# FiltroRF.net
KiCad netlist of a schematic drawn in Altium Designer
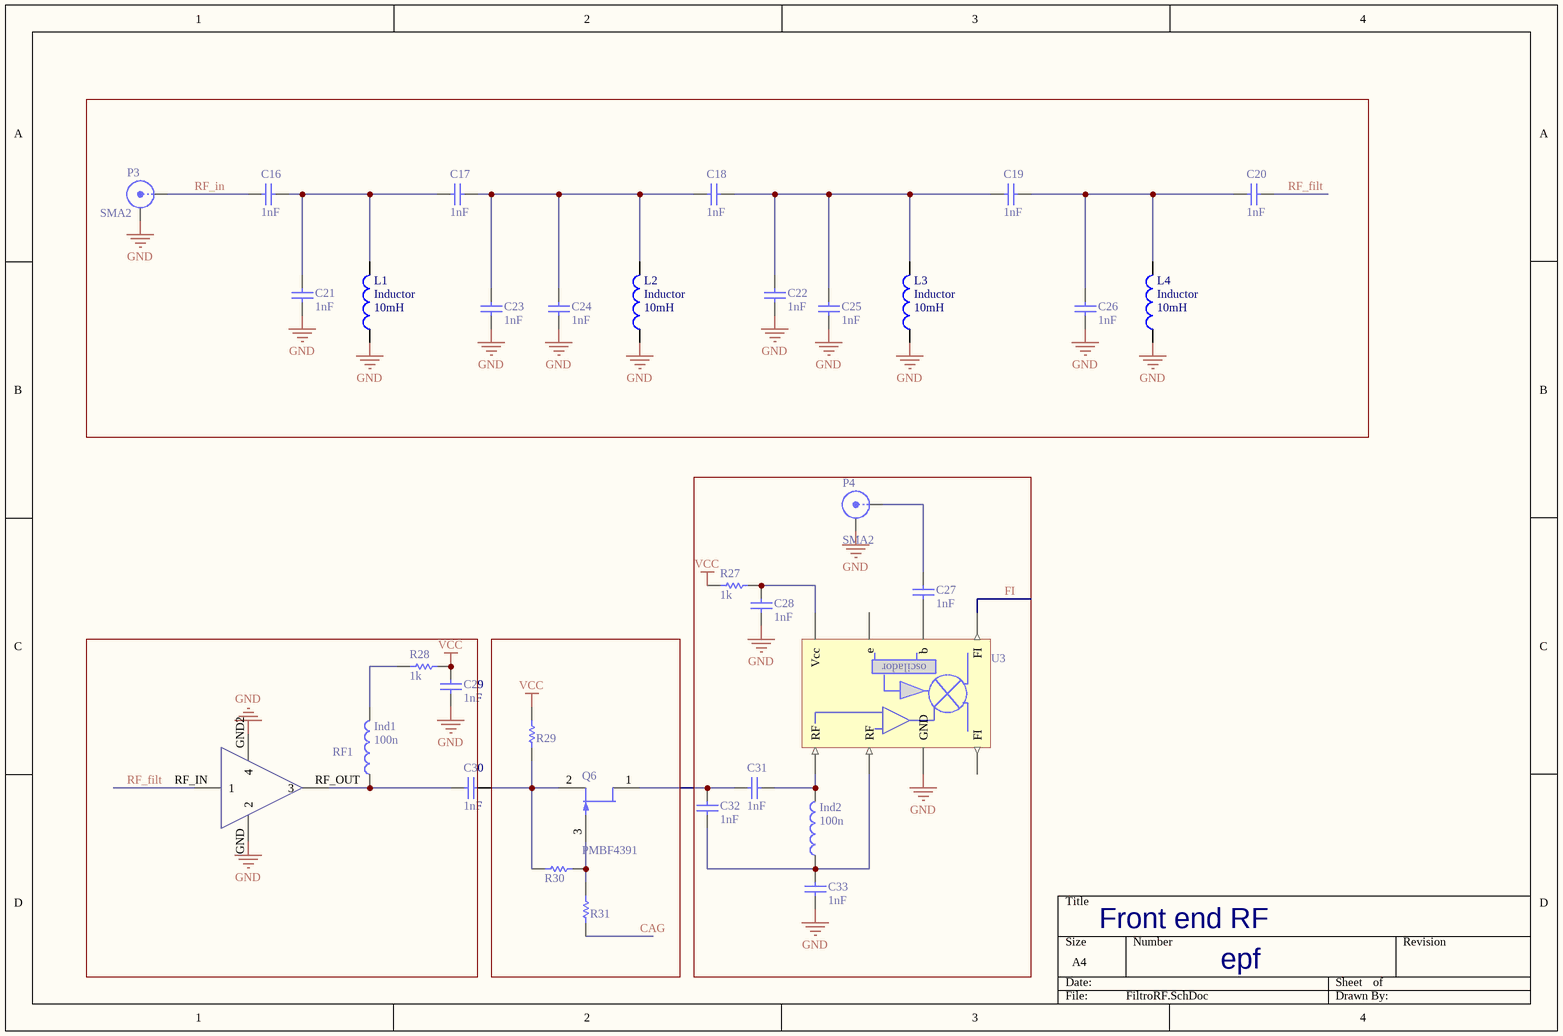
[diagram p0: FiltroRF.SchDoc]

(export (version "E")
  (design (tool "Eeschema 10.0.6"))
  (components
    (comp (ref "C16")
      (value "1nF")
      (footprint "0805_CAP")
      (fields (field (name "Comment") "Capacitor"))
      (libsource (lib "epf") (part "Cap"))
    )
    (comp (ref "C17")
      (value "1nF")
      (footprint "0805_CAP")
      (fields (field (name "Comment") "Capacitor"))
      (libsource (lib "epf") (part "Cap"))
    )
    (comp (ref "C18")
      (value "1nF")
      (footprint "0805_CAP")
      (fields (field (name "Comment") "Capacitor"))
      (libsource (lib "epf") (part "Cap"))
    )
    (comp (ref "C19")
      (value "1nF")
      (footprint "0805_CAP")
      (fields (field (name "Comment") "Capacitor"))
      (libsource (lib "epf") (part "Cap"))
    )
    (comp (ref "C20")
      (value "1nF")
      (footprint "0805_CAP")
      (fields (field (name "Comment") "Capacitor"))
      (libsource (lib "epf") (part "Cap"))
    )
    (comp (ref "C21")
      (value "1nF")
      (footprint "0805_CAP")
      (fields (field (name "Comment") "Capacitor"))
      (libsource (lib "epf") (part "Cap"))
    )
    (comp (ref "C22")
      (value "1nF")
      (footprint "0805_CAP")
      (fields (field (name "Comment") "Capacitor"))
      (libsource (lib "epf") (part "Cap"))
    )
    (comp (ref "C23")
      (value "1nF")
      (footprint "0805_CAP")
      (fields (field (name "Comment") "Capacitor"))
      (libsource (lib "epf") (part "Cap"))
    )
    (comp (ref "C24")
      (value "1nF")
      (footprint "0805_CAP")
      (fields (field (name "Comment") "Capacitor"))
      (libsource (lib "epf") (part "Cap"))
    )
    (comp (ref "C25")
      (value "1nF")
      (footprint "0805_CAP")
      (fields (field (name "Comment") "Capacitor"))
      (libsource (lib "epf") (part "Cap"))
    )
    (comp (ref "C26")
      (value "1nF")
      (footprint "0805_CAP")
      (fields (field (name "Comment") "Capacitor"))
      (libsource (lib "epf") (part "Cap"))
    )
    (comp (ref "C27")
      (value "1nF")
      (footprint "0805_CAP")
      (fields (field (name "Comment") "Capacitor"))
      (libsource (lib "epf") (part "Cap"))
    )
    (comp (ref "C28")
      (value "1nF")
      (footprint "0805_CAP")
      (fields (field (name "Comment") "Capacitor"))
      (libsource (lib "epf") (part "Cap"))
    )
    (comp (ref "C29")
      (value "1nF")
      (footprint "0805_CAP")
      (fields (field (name "Comment") "Capacitor"))
      (libsource (lib "epf") (part "Cap"))
    )
    (comp (ref "C30")
      (value "1nF")
      (footprint "0805_CAP")
      (fields (field (name "Comment") "Capacitor"))
      (libsource (lib "epf") (part "Cap"))
    )
    (comp (ref "C31")
      (value "1nF")
      (footprint "0805_CAP")
      (fields (field (name "Comment") "Capacitor"))
      (libsource (lib "epf") (part "Cap"))
    )
    (comp (ref "C32")
      (value "1nF")
      (footprint "0805_CAP")
      (fields (field (name "Comment") "Capacitor"))
      (libsource (lib "epf") (part "Cap"))
    )
    (comp (ref "C33")
      (value "1nF")
      (footprint "0805_CAP")
      (fields (field (name "Comment") "Capacitor"))
      (libsource (lib "epf") (part "Cap"))
    )
    (comp (ref "Ind1")
      (value "Ind2")
      (footprint "NTH12_2")
      (fields (field (name "VALOR") "100n"))
      (libsource (lib "epf") (part "Ind2"))
    )
    (comp (ref "Ind2")
      (value "Ind2")
      (footprint "Ind_3mm")
      (fields (field (name "VALOR") "100n"))
      (libsource (lib "epf") (part "Ind2"))
    )
    (comp (ref "L1")
      (value "Inductor")
      (footprint "INDC3216AL")
      (fields (field (name "ALTIUM_VALUE") "10mH") (field (name "PUBLISHER") "Altium Limited"))
      (libsource (lib "Miscellaneous Devices") (part "Inductor"))
    )
    (comp (ref "L2")
      (value "Inductor")
      (footprint "INDC3216AL")
      (fields (field (name "ALTIUM_VALUE") "10mH") (field (name "PUBLISHER") "Altium Limited"))
      (libsource (lib "Miscellaneous Devices") (part "Inductor"))
    )
    (comp (ref "L3")
      (value "Inductor")
      (footprint "INDC3216AL")
      (fields (field (name "ALTIUM_VALUE") "10mH") (field (name "PUBLISHER") "Altium Limited"))
      (libsource (lib "Miscellaneous Devices") (part "Inductor"))
    )
    (comp (ref "L4")
      (value "Inductor")
      (footprint "INDC3216AL")
      (fields (field (name "ALTIUM_VALUE") "10mH") (field (name "PUBLISHER") "Altium Limited"))
      (libsource (lib "Miscellaneous Devices") (part "Inductor"))
    )
    (comp (ref "P3")
      (value "SMA2")
      (footprint "SMAL_Antena")
      (description "BNC Elbow Connector")
      (fields (field (name "PUBLISHER") "Altium Limited"))
      (libsource (lib "epf") (part "SMA2"))
    )
    (comp (ref "P4")
      (value "SMA2")
      (footprint "SMAL2")
      (description "BNC Elbow Connector")
      (fields (field (name "PUBLISHER") "Altium Limited"))
      (libsource (lib "epf") (part "SMA2"))
    )
    (comp (ref "Q6")
      (value "PMBF4391")
      (footprint "SOT23")
      (description "N-channel Silicon Junction Field-effect Transistor")
      (fields (field (name "PUBLISHER") "Altium Limited"))
      (libsource (lib "Philips Discrete JFET") (part "PMBF4391"))
    )
    (comp (ref "R27")
      (value "1k")
      (footprint "0805_RES")
      (fields (field (name "Comment") "Resistor"))
      (libsource (lib "epf") (part "Res"))
    )
    (comp (ref "R28")
      (value "1k")
      (footprint "0805_RES")
      (fields (field (name "Comment") "Resistor"))
      (libsource (lib "epf") (part "Res"))
    )
    (comp (ref "R29") (value "Resistor") (footprint "0805_RES") (libsource (lib "epf") (part "Res")))
    (comp (ref "R30") (value "Resistor") (footprint "0805_RES") (libsource (lib "epf") (part "Res")))
    (comp (ref "R31") (value "Resistor") (footprint "0805_RES") (libsource (lib "epf") (part "Res")))
    (comp (ref "RF1") (value "MAR-1SM") (footprint "WW107") (libsource (lib "epf") (part "MAR-1SM")))
    (comp (ref "U3")
      (value "SA602")
      (footprint "SO-8_2")
      (description "Mezclador 500MHz")
      (libsource (lib "epf") (part "SA602A"))
    )
  )
  (nets
    (net (code "1") (name "/CAG") (class "Default")
      (node (ref "R31") (pin "1") (pinfunction "1_1") (pintype "passive"))
    )
    (net (code "2") (name "/FI") (class "Default")
      (node (ref "U3") (pin "5") (pinfunction "FI_5") (pintype "output"))
    )
    (net (code "3") (name "/RF_filt") (class "Default")
      (node (ref "C20") (pin "1") (pinfunction "1_1") (pintype "passive"))
      (node (ref "RF1") (pin "RF_IN") (pinfunction "1_RF_IN") (pintype "passive"))
    )
    (net (code "4") (name "/RF_in") (class "Default")
      (node (ref "C16") (pin "2") (pinfunction "2_2") (pintype "passive"))
      (node (ref "P3") (pin "1") (pinfunction "X_1") (pintype "passive"))
    )
    (net (code "5") (name "GND") (class "Default")
      (node (ref "C21") (pin "2") (pinfunction "2_2") (pintype "passive"))
      (node (ref "C22") (pin "1") (pinfunction "1_1") (pintype "passive"))
      (node (ref "C23") (pin "1") (pinfunction "1_1") (pintype "passive"))
      (node (ref "C24") (pin "1") (pinfunction "1_1") (pintype "passive"))
      (node (ref "C25") (pin "1") (pinfunction "1_1") (pintype "passive"))
      (node (ref "C26") (pin "2") (pinfunction "2_2") (pintype "passive"))
      (node (ref "C28") (pin "1") (pinfunction "1_1") (pintype "passive"))
      (node (ref "C29") (pin "1") (pinfunction "1_1") (pintype "passive"))
      (node (ref "C33") (pin "2") (pinfunction "2_2") (pintype "passive"))
      (node (ref "L1") (pin "1") (pinfunction "1_1") (pintype "passive"))
      (node (ref "L2") (pin "1") (pinfunction "1_1") (pintype "passive"))
      (node (ref "L3") (pin "1") (pinfunction "1_1") (pintype "passive"))
      (node (ref "L4") (pin "1") (pinfunction "1_1") (pintype "passive"))
      (node (ref "P3") (pin "0") (pinfunction "Y_0") (pintype "passive"))
      (node (ref "P4") (pin "0") (pinfunction "Y_0") (pintype "passive"))
      (node (ref "RF1") (pin "GND") (pinfunction "2_GND") (pintype "passive"))
      (node (ref "RF1") (pin "GND2") (pinfunction "4_GND2") (pintype "passive"))
      (node (ref "U3") (pin "3") (pinfunction "GND_3") (pintype "passive"))
    )
    (net (code "6") (name "Net-(C16-Pad1)") (class "Default")
      (node (ref "C16") (pin "1") (pinfunction "1_1") (pintype "passive"))
      (node (ref "C17") (pin "2") (pinfunction "2_2") (pintype "passive"))
      (node (ref "C21") (pin "1") (pinfunction "1_1") (pintype "passive"))
      (node (ref "L1") (pin "2") (pinfunction "2_2") (pintype "passive"))
    )
    (net (code "7") (name "Net-(C17-Pad1)") (class "Default")
      (node (ref "C17") (pin "1") (pinfunction "1_1") (pintype "passive"))
      (node (ref "C18") (pin "1") (pinfunction "1_1") (pintype "passive"))
      (node (ref "C23") (pin "2") (pinfunction "2_2") (pintype "passive"))
      (node (ref "C24") (pin "2") (pinfunction "2_2") (pintype "passive"))
      (node (ref "L2") (pin "2") (pinfunction "2_2") (pintype "passive"))
    )
    (net (code "8") (name "Net-(C18-Pad2)") (class "Default")
      (node (ref "C18") (pin "2") (pinfunction "2_2") (pintype "passive"))
      (node (ref "C19") (pin "1") (pinfunction "1_1") (pintype "passive"))
      (node (ref "C22") (pin "2") (pinfunction "2_2") (pintype "passive"))
      (node (ref "C25") (pin "2") (pinfunction "2_2") (pintype "passive"))
      (node (ref "L3") (pin "2") (pinfunction "2_2") (pintype "passive"))
    )
    (net (code "9") (name "Net-(C19-Pad2)") (class "Default")
      (node (ref "C19") (pin "2") (pinfunction "2_2") (pintype "passive"))
      (node (ref "C20") (pin "2") (pinfunction "2_2") (pintype "passive"))
      (node (ref "C26") (pin "1") (pinfunction "1_1") (pintype "passive"))
      (node (ref "L4") (pin "2") (pinfunction "2_2") (pintype "passive"))
    )
    (net (code "10") (name "Net-(C31-Pad1)") (class "Default")
      (node (ref "C31") (pin "1") (pinfunction "1_1") (pintype "passive"))
      (node (ref "Ind2") (pin "2") (pinfunction "2_2") (pintype "passive"))
      (node (ref "U3") (pin "1") (pinfunction "RF_1") (pintype "input"))
    )
    (net (code "11") (name "Net-(C32-Pad2)") (class "Default")
      (node (ref "C32") (pin "2") (pinfunction "2_2") (pintype "passive"))
      (node (ref "C33") (pin "1") (pinfunction "1_1") (pintype "passive"))
      (node (ref "Ind2") (pin "1") (pinfunction "1_1") (pintype "passive"))
      (node (ref "U3") (pin "2") (pinfunction "RF_2") (pintype "input"))
    )
    (net (code "12") (name "Net-(Ind1-Pad2)") (class "Default")
      (node (ref "Ind1") (pin "2") (pinfunction "2_2") (pintype "passive"))
      (node (ref "R28") (pin "1") (pinfunction "1_1") (pintype "passive"))
    )
    (net (code "13") (name "Net-(P4-X)") (class "Default")
      (node (ref "C27") (pin "2") (pinfunction "2_2") (pintype "passive"))
      (node (ref "P4") (pin "1") (pinfunction "X_1") (pintype "passive"))
    )
    (net (code "14") (name "Net-(Q6-D)") (class "Default")
      (node (ref "C31") (pin "2") (pinfunction "2_2") (pintype "passive"))
      (node (ref "C32") (pin "1") (pinfunction "1_1") (pintype "passive"))
      (node (ref "Q6") (pin "1") (pinfunction "D_1") (pintype "passive"))
    )
    (net (code "15") (name "Net-(Q6-G)") (class "Default")
      (node (ref "Q6") (pin "3") (pinfunction "G_3") (pintype "passive"))
      (node (ref "R30") (pin "1") (pinfunction "1_1") (pintype "passive"))
      (node (ref "R31") (pin "2") (pinfunction "2_2") (pintype "passive"))
    )
    (net (code "16") (name "Net-(Q6-S)") (class "Default")
      (node (ref "C30") (pin "1") (pinfunction "1_1") (pintype "passive"))
      (node (ref "Q6") (pin "2") (pinfunction "S_2") (pintype "passive"))
      (node (ref "R29") (pin "2") (pinfunction "2_2") (pintype "passive"))
      (node (ref "R30") (pin "2") (pinfunction "2_2") (pintype "passive"))
    )
    (net (code "17") (name "Net-(RF1-3)") (class "Default")
      (node (ref "C30") (pin "2") (pinfunction "2_2") (pintype "passive"))
      (node (ref "Ind1") (pin "1") (pinfunction "1_1") (pintype "passive"))
      (node (ref "RF1") (pin "RF_OUT") (pinfunction "3_RF_OUT") (pintype "passive"))
    )
    (net (code "18") (name "Net-(U3-Vcc)") (class "Default")
      (node (ref "C28") (pin "2") (pinfunction "2_2") (pintype "passive"))
      (node (ref "R27") (pin "2") (pinfunction "2_2") (pintype "passive"))
      (node (ref "U3") (pin "8") (pinfunction "Vcc_8") (pintype "passive"))
    )
    (net (code "19") (name "Net-(U3-b)") (class "Default")
      (node (ref "C27") (pin "1") (pinfunction "1_1") (pintype "passive"))
      (node (ref "U3") (pin "6") (pinfunction "b_6") (pintype "passive"))
    )
    (net (code "20") (name "VCC") (class "Default")
      (node (ref "C29") (pin "2") (pinfunction "2_2") (pintype "passive"))
      (node (ref "R27") (pin "1") (pinfunction "1_1") (pintype "passive"))
      (node (ref "R28") (pin "2") (pinfunction "2_2") (pintype "passive"))
      (node (ref "R29") (pin "1") (pinfunction "1_1") (pintype "passive"))
    )
    (net (code "21") (name "unconnected-(U3-FI-Pad4)") (class "Default")
      (node (ref "U3") (pin "4") (pinfunction "FI_4") (pintype "output"))
    )
    (net (code "22") (name "unconnected-(U3-e-Pad7)") (class "Default")
      (node (ref "U3") (pin "7") (pinfunction "e_7") (pintype "passive"))
    )
  )
)
